# SCH_Card_2024-05-24.net
KiCad netlist of a schematic drawn in EasyEDA
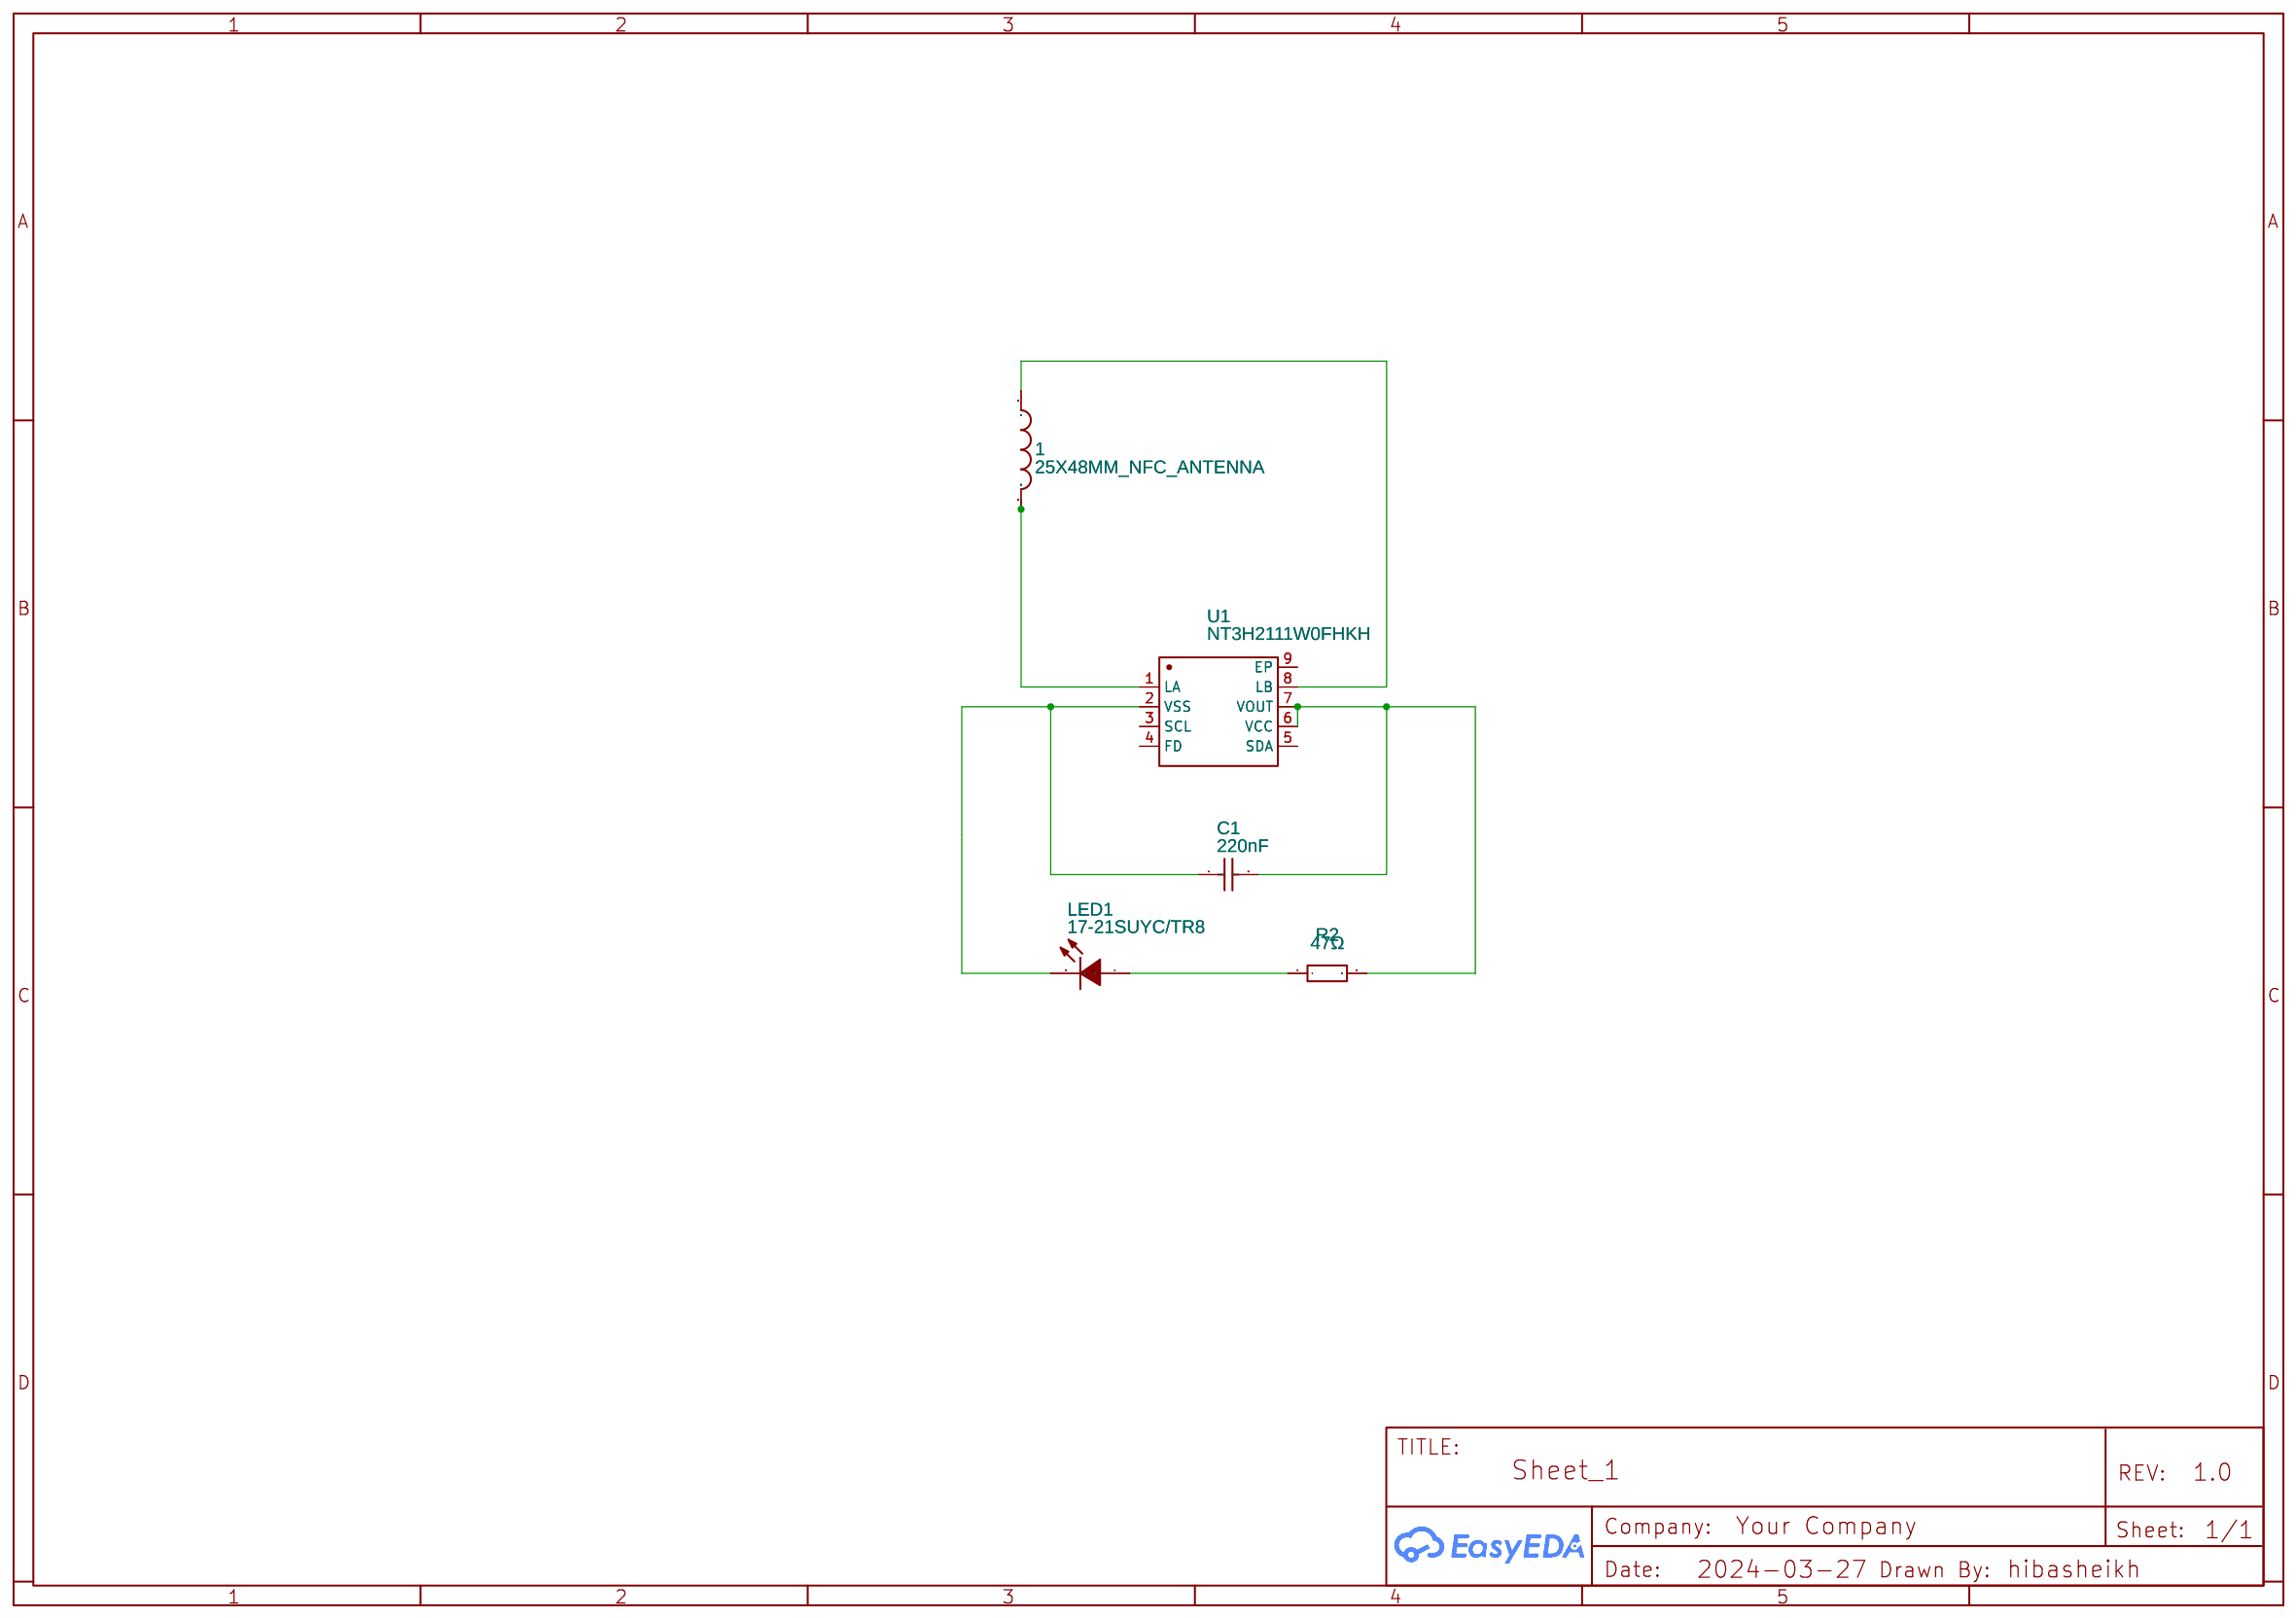
[diagram p0: schematic sheet]

(export (version "E")
  (design (tool "Eeschema 10.0.6"))
  (components
    (comp (ref "1") (value "25X48MM_NFC_ANTENNA") (libsource (lib "") (part "25X48MM_NFC_ANTENNA")))
    (comp (ref "C1")
      (value "220nF")
      (fields
        (field (name "Manufacturer Part") "CL10B224KA8NNNC")
        (field (name "Manufacturer") "SAMSUNG(三星)")
      )
      (libsource (lib "") (part "CL10B224KA8NNNC"))
    )
    (comp (ref "LED1")
      (value "17-21SUYC/TR8")
      (fields (field (name "Manufacturer Part") "KT-0805黄灯") (field (name "Manufacturer") "KENTO"))
      (libsource (lib "") (part "17-21SUYC/TR8"))
    )
    (comp (ref "R2")
      (value "47Ω")
      (fields
        (field (name "Manufacturer Part") "0603WAF470JT5E")
        (field (name "Manufacturer") "UNI-ROYAL(厚声)")
      )
      (libsource (lib "") (part "0603WAF470JT5E"))
    )
    (comp (ref "U1")
      (value "NT3H2111W0FHKH")
      (fields (field (name "Manufacturer") "NXP(恩智浦)"))
      (libsource (lib "") (part "NT3H2111W0FHKH"))
    )
  )
  (nets
    (net (code "1") (name "Net-(LED1-+)") (class "Default")
      (node (ref "LED1") (pin "1") (pinfunction "+_1") (pintype "unspecified"))
      (node (ref "R2") (pin "1") (pinfunction "1_1") (pintype "input"))
    )
    (net (code "2") (name "Net-(LED1--)") (class "Default")
      (node (ref "C1") (pin "1") (pinfunction "1_1") (pintype "input"))
      (node (ref "LED1") (pin "2") (pinfunction "-_2") (pintype "unspecified"))
      (node (ref "U1") (pin "2") (pinfunction "VSS_2") (pintype "unspecified"))
    )
    (net (code "3") (name "Net-(U1-LA)") (class "Default")
      (node (ref "1") (pin "P$2") (pinfunction "P$2_P$2") (pintype "bidirectional"))
      (node (ref "U1") (pin "1") (pinfunction "LA_1") (pintype "unspecified"))
    )
    (net (code "4") (name "Net-(U1-LB)") (class "Default")
      (node (ref "1") (pin "P$1") (pinfunction "P$1_P$1") (pintype "bidirectional"))
      (node (ref "U1") (pin "8") (pinfunction "LB_8") (pintype "unspecified"))
    )
    (net (code "5") (name "Net-(U1-VCC)") (class "Default")
      (node (ref "C1") (pin "2") (pinfunction "2_2") (pintype "input"))
      (node (ref "R2") (pin "2") (pinfunction "2_2") (pintype "input"))
      (node (ref "U1") (pin "6") (pinfunction "VCC_6") (pintype "unspecified"))
      (node (ref "U1") (pin "7") (pinfunction "VOUT_7") (pintype "unspecified"))
    )
    (net (code "6") (name "unconnected-(U1-EP-Pad9)") (class "Default")
      (node (ref "U1") (pin "9") (pinfunction "EP_9") (pintype "unspecified"))
    )
    (net (code "7") (name "unconnected-(U1-FD-Pad4)") (class "Default")
      (node (ref "U1") (pin "4") (pinfunction "FD_4") (pintype "unspecified"))
    )
    (net (code "8") (name "unconnected-(U1-SCL-Pad3)") (class "Default")
      (node (ref "U1") (pin "3") (pinfunction "SCL_3") (pintype "unspecified"))
    )
    (net (code "9") (name "unconnected-(U1-SDA-Pad5)") (class "Default")
      (node (ref "U1") (pin "5") (pinfunction "SDA_5") (pintype "unspecified"))
    )
  )
)
